# Li-IonBatteryManager.net
KiCad netlist of a schematic drawn in Altium Designer
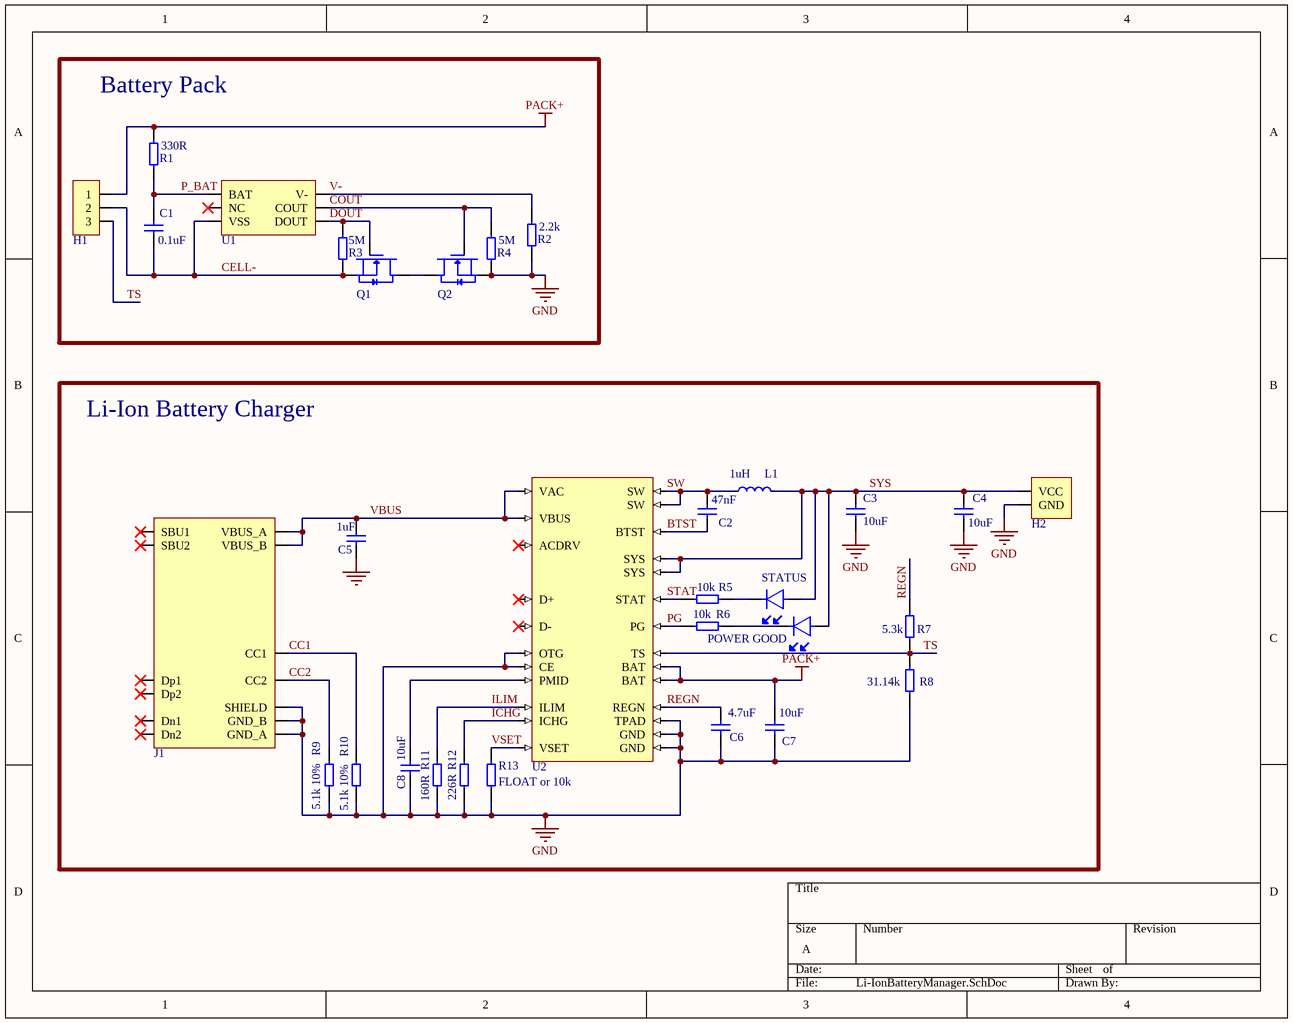
[diagram p0: Li-IonBatteryManager.SchDoc]

(export (version "E")
  (design (tool "Eeschema 10.0.6"))
  (components
    (comp (ref "C1")
      (value "0.1uF")
      (footprint "0603 Capacitor")
      (libsource (lib "MoldsvorLibrary") (part "Capacitor"))
    )
    (comp (ref "C2")
      (value "47nF")
      (footprint "0603 Capacitor")
      (libsource (lib "MoldsvorLibrary") (part "Capacitor"))
    )
    (comp (ref "C3")
      (value "10uF")
      (footprint "0603 Capacitor")
      (libsource (lib "MoldsvorLibrary") (part "Capacitor"))
    )
    (comp (ref "C4")
      (value "10uF")
      (footprint "0603 Capacitor")
      (libsource (lib "MoldsvorLibrary") (part "Capacitor"))
    )
    (comp (ref "C5")
      (value "1uF")
      (footprint "0603 Capacitor")
      (libsource (lib "MoldsvorLibrary") (part "Capacitor"))
    )
    (comp (ref "C6")
      (value "4.7uF")
      (footprint "0603 Capacitor")
      (libsource (lib "MoldsvorLibrary") (part "Capacitor"))
    )
    (comp (ref "C7")
      (value "10uF")
      (footprint "0603 Capacitor")
      (libsource (lib "MoldsvorLibrary") (part "Capacitor"))
    )
    (comp (ref "C8")
      (value "10uF")
      (footprint "0603 Capacitor")
      (libsource (lib "MoldsvorLibrary") (part "Capacitor"))
    )
    (comp (ref "D1") (value "STATUS") (footprint "0603 LED") (libsource (lib "MoldsvorLibrary") (part "LED")))
    (comp (ref "D2")
      (value "POWER GOOD")
      (footprint "0603 LED")
      (libsource (lib "MoldsvorLibrary") (part "LED"))
    )
    (comp (ref "H1")
      (value "22-05-7035")
      (footprint "Molex Header 3")
      (description "Header 2.5mm SPOX,  WTB,  RA,  F/lock,  3w")
      (libsource (lib "MoldsvorLibrary") (part "22-05-7035"))
    )
    (comp (ref "H2")
      (value "Header 2x1")
      (footprint "HEADER 2x1")
      (libsource (lib "MoldsvorLibrary") (part "Header 2x1"))
    )
    (comp (ref "J1")
      (value "2137160001")
      (footprint "USB TYPE C Molex")
      (description "Type C Receptacle DIP 16PIN")
      (libsource (lib "MoldsvorBatteryLibrary") (part "2137160001"))
    )
    (comp (ref "L1")
      (value "1uH")
      (footprint "SRP2510A")
      (description "BOURNS - SRP2510A-1R0M - INDUCTOR, 1UH, 3A, 20%, SHIELDED")
      (fields (field (name "TOLERANCE") "20%"))
      (libsource (lib "MoldsvorLibrary") (part "SRP2510A-1R0M"))
    )
    (comp (ref "Q1")
      (value "CSD16406Q3")
      (footprint "CSD16406Q3")
      (description "TEXAS INSTRUMENTS - CSD16406Q3 - N CHANNEL MOSFET, 25V, 60A, SON")
      (libsource (lib "MoldsvorLibrary") (part "CSD16406Q3"))
    )
    (comp (ref "Q2")
      (value "CSD16406Q3")
      (footprint "CSD16406Q3")
      (description "TEXAS INSTRUMENTS - CSD16406Q3 - N CHANNEL MOSFET, 25V, 60A, SON")
      (libsource (lib "MoldsvorLibrary") (part "CSD16406Q3"))
    )
    (comp (ref "R1")
      (value "330R")
      (footprint "0603 Resistor")
      (libsource (lib "MoldsvorPassivesLibrary") (part "Resistor"))
    )
    (comp (ref "R2")
      (value "2.2k")
      (footprint "0603 Resistor")
      (libsource (lib "MoldsvorPassivesLibrary") (part "Resistor"))
    )
    (comp (ref "R3")
      (value "5M")
      (footprint "0603 Resistor")
      (libsource (lib "MoldsvorPassivesLibrary") (part "Resistor"))
    )
    (comp (ref "R4")
      (value "5M")
      (footprint "0603 Resistor")
      (libsource (lib "MoldsvorPassivesLibrary") (part "Resistor"))
    )
    (comp (ref "R5")
      (value "10k")
      (footprint "0603 Resistor")
      (libsource (lib "MoldsvorLibrary") (part "Resistor"))
    )
    (comp (ref "R6")
      (value "10k")
      (footprint "0603 Resistor")
      (libsource (lib "MoldsvorLibrary") (part "Resistor"))
    )
    (comp (ref "R7")
      (value "5.3k")
      (footprint "0603 Resistor")
      (libsource (lib "MoldsvorLibrary") (part "Resistor"))
    )
    (comp (ref "R8")
      (value "31.14k")
      (footprint "0603 Resistor")
      (libsource (lib "MoldsvorLibrary") (part "Resistor"))
    )
    (comp (ref "R9")
      (value "5.1k 10%")
      (footprint "0603 Resistor")
      (libsource (lib "MoldsvorLibrary") (part "Resistor"))
    )
    (comp (ref "R10")
      (value "5.1k 10%")
      (footprint "0603 Resistor")
      (libsource (lib "MoldsvorLibrary") (part "Resistor"))
    )
    (comp (ref "R11")
      (value "160R")
      (footprint "0603 Resistor")
      (libsource (lib "MoldsvorLibrary") (part "Resistor"))
    )
    (comp (ref "R12")
      (value "226R")
      (footprint "0603 Resistor")
      (libsource (lib "MoldsvorLibrary") (part "Resistor"))
    )
    (comp (ref "R13")
      (value "FLOAT or 10k")
      (footprint "0603 Resistor")
      (libsource (lib "MoldsvorLibrary") (part "Resistor"))
    )
    (comp (ref "U1")
      (value "BQ29700DSET")
      (footprint "BQ297xx")
      (description "Li-Ion/Li Polymer Advanced Single-Cell Battery Protector IC Family 6-WSON -40 to 85")
      (libsource (lib "MoldsvorLibrary") (part "BQ29700DSET"))
    )
    (comp (ref "U2")
      (value "BQ25616JRTWR")
      (footprint "BQ25616")
      (libsource (lib "MoldsvorBatteryLibrary") (part "BQ25616JRTWR"))
    )
  )
  (nets
    (net (code "1") (name "/BTST") (class "Default")
      (node (ref "C2") (pin "1") (pinfunction "1_1") (pintype "passive"))
      (node (ref "U2") (pin "21") (pinfunction "BTST_21") (pintype "input"))
    )
    (net (code "2") (name "/CC1") (class "Default")
      (node (ref "J1") (pin "A5") (pinfunction "CC1_A5") (pintype "passive"))
      (node (ref "R10") (pin "2") (pintype "passive"))
    )
    (net (code "3") (name "/CC2") (class "Default")
      (node (ref "J1") (pin "B5") (pinfunction "CC2_B5") (pintype "passive"))
      (node (ref "R9") (pin "2") (pintype "passive"))
    )
    (net (code "4") (name "/CELL-") (class "Default")
      (node (ref "C1") (pin "1") (pinfunction "1_1") (pintype "passive"))
      (node (ref "H1") (pin "2") (pinfunction "2_2") (pintype "passive"))
      (node (ref "Q1") (pin "1") (pinfunction "1_1") (pintype "passive"))
      (node (ref "R3") (pin "1") (pintype "passive"))
      (node (ref "U1") (pin "4") (pinfunction "VSS_4") (pintype "passive"))
    )
    (net (code "5") (name "/COUT") (class "Default")
      (node (ref "Q2") (pin "4") (pinfunction "4_4") (pintype "passive"))
      (node (ref "R4") (pin "2") (pintype "passive"))
      (node (ref "U1") (pin "2") (pinfunction "COUT_2") (pintype "passive"))
    )
    (net (code "6") (name "/DOUT") (class "Default")
      (node (ref "Q1") (pin "4") (pinfunction "4_4") (pintype "passive"))
      (node (ref "R3") (pin "2") (pintype "passive"))
      (node (ref "U1") (pin "3") (pinfunction "DOUT_3") (pintype "passive"))
    )
    (net (code "7") (name "/ICHG") (class "Default")
      (node (ref "R12") (pin "2") (pintype "passive"))
      (node (ref "U2") (pin "10") (pinfunction "ICHG_10") (pintype "input"))
    )
    (net (code "8") (name "/ILIM") (class "Default")
      (node (ref "R11") (pin "2") (pintype "passive"))
      (node (ref "U2") (pin "8") (pinfunction "ILIM_8") (pintype "input"))
    )
    (net (code "9") (name "/PG") (class "Default")
      (node (ref "R6") (pin "1") (pintype "passive"))
      (node (ref "U2") (pin "7") (pinfunction "PG_7") (pintype "input"))
    )
    (net (code "10") (name "/P_BAT") (class "Default")
      (node (ref "C1") (pin "2") (pinfunction "2_2") (pintype "passive"))
      (node (ref "R1") (pin "1") (pintype "passive"))
      (node (ref "U1") (pin "5") (pinfunction "BAT_5") (pintype "passive"))
    )
    (net (code "11") (name "/REGN") (class "Default")
      (node (ref "C6") (pin "2") (pinfunction "2_2") (pintype "passive"))
      (node (ref "R7") (pin "2") (pintype "passive"))
      (node (ref "U2") (pin "22") (pinfunction "REGN_22") (pintype "input"))
    )
    (net (code "12") (name "/STAT") (class "Default")
      (node (ref "R5") (pin "1") (pintype "passive"))
      (node (ref "U2") (pin "5") (pinfunction "STAT_5") (pintype "input"))
    )
    (net (code "13") (name "/SW") (class "Default")
      (node (ref "C2") (pin "2") (pinfunction "2_2") (pintype "passive"))
      (node (ref "L1") (pin "1") (pinfunction "1_1") (pintype "passive"))
      (node (ref "U2") (pin "19") (pinfunction "SW_19") (pintype "input"))
      (node (ref "U2") (pin "20") (pinfunction "SW_20") (pintype "input"))
    )
    (net (code "14") (name "/SYS") (class "Default")
      (node (ref "C3") (pin "2") (pinfunction "2_2") (pintype "passive"))
      (node (ref "C4") (pin "2") (pinfunction "2_2") (pintype "passive"))
      (node (ref "D1") (pin "1") (pintype "passive"))
      (node (ref "D2") (pin "1") (pintype "passive"))
      (node (ref "H2") (pin "1") (pinfunction "VCC_1") (pintype "passive"))
      (node (ref "L1") (pin "2") (pinfunction "2_2") (pintype "passive"))
      (node (ref "U2") (pin "15") (pinfunction "SYS_15") (pintype "input"))
      (node (ref "U2") (pin "16") (pinfunction "SYS_16") (pintype "input"))
    )
    (net (code "15") (name "/TS") (class "Default")
      (node (ref "H1") (pin "3") (pinfunction "3_3") (pintype "passive"))
      (node (ref "R7") (pin "1") (pintype "passive"))
      (node (ref "R8") (pin "2") (pintype "passive"))
      (node (ref "U2") (pin "11") (pinfunction "TS_11") (pintype "input"))
    )
    (net (code "16") (name "/V-") (class "Default")
      (node (ref "R2") (pin "2") (pintype "passive"))
      (node (ref "U1") (pin "6") (pinfunction "V-_6") (pintype "passive"))
    )
    (net (code "17") (name "/VBUS") (class "Default")
      (node (ref "C5") (pin "2") (pinfunction "2_2") (pintype "passive"))
      (node (ref "J1") (pin "A4") (pinfunction "VBUS_A_A4") (pintype "passive"))
      (node (ref "J1") (pin "B4") (pinfunction "VBUS_B_B4") (pintype "passive"))
      (node (ref "U2") (pin "1") (pinfunction "VAC_1") (pintype "input"))
      (node (ref "U2") (pin "24") (pinfunction "VBUS_24") (pintype "input"))
    )
    (net (code "18") (name "/VSET") (class "Default")
      (node (ref "R13") (pin "2") (pintype "passive"))
      (node (ref "U2") (pin "12") (pinfunction "VSET_12") (pintype "input"))
    )
    (net (code "19") (name "GND") (class "Default")
      (node (ref "C3") (pin "1") (pinfunction "1_1") (pintype "passive"))
      (node (ref "C4") (pin "1") (pinfunction "1_1") (pintype "passive"))
      (node (ref "C5") (pin "1") (pinfunction "1_1") (pintype "passive"))
      (node (ref "C6") (pin "1") (pinfunction "1_1") (pintype "passive"))
      (node (ref "C7") (pin "1") (pinfunction "1_1") (pintype "passive"))
      (node (ref "C8") (pin "1") (pinfunction "1_1") (pintype "passive"))
      (node (ref "H2") (pin "2") (pinfunction "GND_2") (pintype "passive"))
      (node (ref "J1") (pin "A1") (pinfunction "GND_A_A1") (pintype "passive"))
      (node (ref "J1") (pin "B1") (pinfunction "GND_B_B1") (pintype "passive"))
      (node (ref "J1") (pin "SHIELD") (pinfunction "SHIELD_SHIELD") (pintype "passive"))
      (node (ref "Q2") (pin "1") (pinfunction "1_1") (pintype "passive"))
      (node (ref "R10") (pin "1") (pintype "passive"))
      (node (ref "R11") (pin "1") (pintype "passive"))
      (node (ref "R12") (pin "1") (pintype "passive"))
      (node (ref "R13") (pin "1") (pintype "passive"))
      (node (ref "R2") (pin "1") (pintype "passive"))
      (node (ref "R4") (pin "1") (pintype "passive"))
      (node (ref "R8") (pin "1") (pintype "passive"))
      (node (ref "R9") (pin "1") (pintype "passive"))
      (node (ref "U2") (pin "17") (pinfunction "GND_17") (pintype "input"))
      (node (ref "U2") (pin "18") (pinfunction "GND_18") (pintype "input"))
      (node (ref "U2") (pin "25") (pinfunction "TPAD_25") (pintype "input"))
      (node (ref "U2") (pin "6") (pinfunction "OTG_6") (pintype "input"))
      (node (ref "U2") (pin "9") (pinfunction "CE_9") (pintype "input"))
    )
    (net (code "20") (name "Net-(D1-Pad2)") (class "Default")
      (node (ref "D1") (pin "2") (pintype "passive"))
      (node (ref "R5") (pin "2") (pintype "passive"))
    )
    (net (code "21") (name "Net-(D2-Pad2)") (class "Default")
      (node (ref "D2") (pin "2") (pintype "passive"))
      (node (ref "R6") (pin "2") (pintype "passive"))
    )
    (net (code "22") (name "Net-(Q1-Pad5)") (class "Default")
      (node (ref "Q1") (pin "5") (pinfunction "5_5") (pintype "passive"))
      (node (ref "Q2") (pin "5") (pinfunction "5_5") (pintype "passive"))
    )
    (net (code "23") (name "Net-(U2-PMID)") (class "Default")
      (node (ref "C8") (pin "2") (pinfunction "2_2") (pintype "passive"))
      (node (ref "U2") (pin "23") (pinfunction "PMID_23") (pintype "input"))
    )
    (net (code "24") (name "PACK+") (class "Default")
      (node (ref "C7") (pin "2") (pinfunction "2_2") (pintype "passive"))
      (node (ref "H1") (pin "1") (pinfunction "1_1") (pintype "passive"))
      (node (ref "R1") (pin "2") (pintype "passive"))
      (node (ref "U2") (pin "13") (pinfunction "BAT_13") (pintype "input"))
      (node (ref "U2") (pin "14") (pinfunction "BAT_14") (pintype "input"))
    )
    (net (code "25") (name "unconnected-(J1-Dn1-PadA7)") (class "Default")
      (node (ref "J1") (pin "A7") (pinfunction "Dn1_A7") (pintype "passive+no_connect"))
    )
    (net (code "26") (name "unconnected-(J1-Dn2-PadB7)") (class "Default")
      (node (ref "J1") (pin "B7") (pinfunction "Dn2_B7") (pintype "passive+no_connect"))
    )
    (net (code "27") (name "unconnected-(J1-Dp1-PadA6)") (class "Default")
      (node (ref "J1") (pin "A6") (pinfunction "Dp1_A6") (pintype "passive+no_connect"))
    )
    (net (code "28") (name "unconnected-(J1-Dp2-PadB6)") (class "Default")
      (node (ref "J1") (pin "B6") (pinfunction "Dp2_B6") (pintype "passive+no_connect"))
    )
    (net (code "29") (name "unconnected-(J1-SBU1-PadA8)") (class "Default")
      (node (ref "J1") (pin "A8") (pinfunction "SBU1_A8") (pintype "passive+no_connect"))
    )
    (net (code "30") (name "unconnected-(J1-SBU2-PadB8)") (class "Default")
      (node (ref "J1") (pin "B8") (pinfunction "SBU2_B8") (pintype "passive+no_connect"))
    )
    (net (code "31") (name "unconnected-(U1-NC-Pad1)") (class "Default")
      (node (ref "U1") (pin "1") (pinfunction "NC_1") (pintype "passive+no_connect"))
    )
    (net (code "32") (name "unconnected-(U2-ACDRV-Pad2)") (class "Default")
      (node (ref "U2") (pin "2") (pinfunction "ACDRV_2") (pintype "input+no_connect"))
    )
    (net (code "33") (name "unconnected-(U2-D+-Pad3)") (class "Default")
      (node (ref "U2") (pin "3") (pinfunction "D+_3") (pintype "input+no_connect"))
    )
    (net (code "34") (name "unconnected-(U2-D--Pad4)") (class "Default")
      (node (ref "U2") (pin "4") (pinfunction "D-_4") (pintype "input+no_connect"))
    )
  )
)
